# Xbee_shield_v15.net
KiCad netlist of a schematic drawn in EAGLE
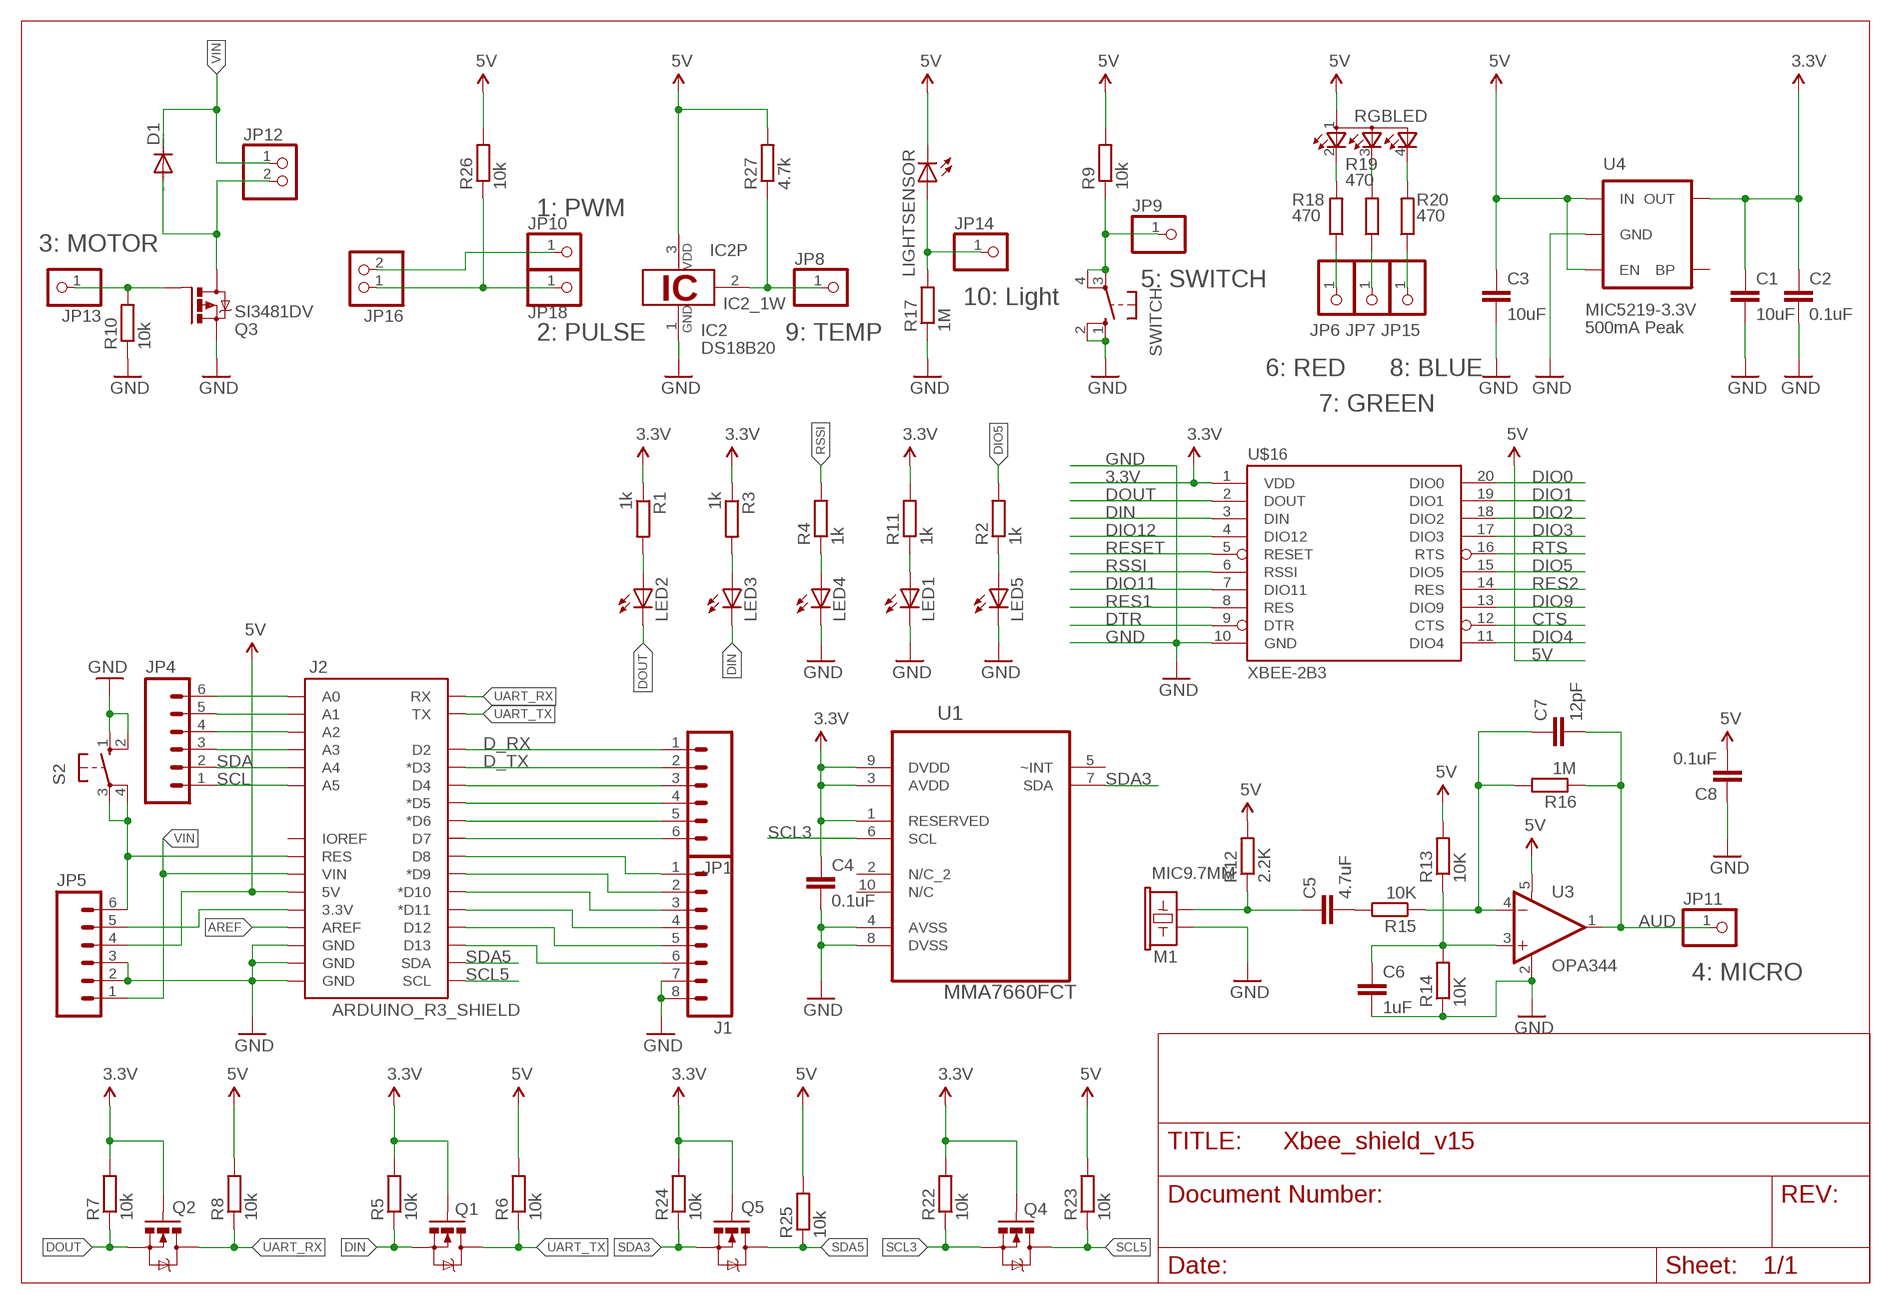
[diagram p0: schematic, sheet 1]

(export (version "E")
  (design (tool "Eeschema 10.0.6"))
  (components
    (comp (ref "C1")
      (value "10uF")
      (footprint "eagle-import:C0805")
      (libsource (lib "eagle-import") (part "C-EUC0805"))
    )
    (comp (ref "C2")
      (value "0.1uF")
      (footprint "eagle-import:C0805")
      (libsource (lib "eagle-import") (part "C-EUC0805"))
    )
    (comp (ref "C3")
      (value "10uF")
      (footprint "eagle-import:C0805")
      (libsource (lib "eagle-import") (part "C-EUC0805"))
    )
    (comp (ref "C4")
      (value "0.1uF")
      (footprint "eagle-import:C0805")
      (libsource (lib "eagle-import") (part "C-EUC0805"))
    )
    (comp (ref "C5")
      (value "4.7uF")
      (footprint "eagle-import:C0805")
      (libsource (lib "eagle-import") (part "C-EUC0805"))
    )
    (comp (ref "C6")
      (value "1uF")
      (footprint "eagle-import:C0805")
      (libsource (lib "eagle-import") (part "C-EUC0805"))
    )
    (comp (ref "C7")
      (value "12pF")
      (footprint "eagle-import:C0805")
      (libsource (lib "eagle-import") (part "C-EUC0805"))
    )
    (comp (ref "C8")
      (value "0.1uF")
      (footprint "eagle-import:C0805")
      (libsource (lib "eagle-import") (part "C-EUC0805"))
    )
    (comp (ref "D1")
      (value "DIODE-DO214AA")
      (footprint "eagle-import:DO214AA")
      (libsource (lib "eagle-import") (part "DIODE-DO214AA"))
    )
    (comp (ref "IC2")
      (value "DS18B20")
      (footprint "eagle-import:TO92-")
      (libsource (lib "eagle-import") (part "DS18B20"))
    )
    (comp (ref "J1")
      (value "M08")
      (footprint "eagle-import:1X08_ROUND")
      (libsource (lib "eagle-import") (part "M08"))
    )
    (comp (ref "J2")
      (value "ARDUINO_R3_SHIELD")
      (footprint "eagle-import:UNO_R3_SHIELD")
      (libsource (lib "eagle-import") (part "ARDUINO_R3_SHIELD"))
    )
    (comp (ref "JP1")
      (value "M06SIP")
      (footprint "eagle-import:1X06")
      (libsource (lib "eagle-import") (part "M06SIP"))
    )
    (comp (ref "JP4")
      (value "M06SIP")
      (footprint "eagle-import:1X06")
      (libsource (lib "eagle-import") (part "M06SIP"))
    )
    (comp (ref "JP5")
      (value "M06SIP")
      (footprint "eagle-import:1X06")
      (libsource (lib "eagle-import") (part "M06SIP"))
    )
    (comp (ref "JP6")
      (value "PINHD-1X1")
      (footprint "eagle-import:1X01")
      (libsource (lib "eagle-import") (part "PINHD-1X1"))
    )
    (comp (ref "JP7")
      (value "PINHD-1X1")
      (footprint "eagle-import:1X01")
      (libsource (lib "eagle-import") (part "PINHD-1X1"))
    )
    (comp (ref "JP8")
      (value "PINHD-1X1")
      (footprint "eagle-import:1X01")
      (libsource (lib "eagle-import") (part "PINHD-1X1"))
    )
    (comp (ref "JP9")
      (value "PINHD-1X1")
      (footprint "eagle-import:1X01")
      (libsource (lib "eagle-import") (part "PINHD-1X1"))
    )
    (comp (ref "JP10")
      (value "PINHD-1X1")
      (footprint "eagle-import:1X01")
      (libsource (lib "eagle-import") (part "PINHD-1X1"))
    )
    (comp (ref "JP11")
      (value "PINHD-1X1")
      (footprint "eagle-import:1X01")
      (libsource (lib "eagle-import") (part "PINHD-1X1"))
    )
    (comp (ref "JP12")
      (value "PINHD-1X2")
      (footprint "eagle-import:1X02")
      (libsource (lib "eagle-import") (part "PINHD-1X2"))
    )
    (comp (ref "JP13")
      (value "PINHD-1X1")
      (footprint "eagle-import:1X01")
      (libsource (lib "eagle-import") (part "PINHD-1X1"))
    )
    (comp (ref "JP14")
      (value "PINHD-1X1")
      (footprint "eagle-import:1X01")
      (libsource (lib "eagle-import") (part "PINHD-1X1"))
    )
    (comp (ref "JP15")
      (value "PINHD-1X1")
      (footprint "eagle-import:1X01")
      (libsource (lib "eagle-import") (part "PINHD-1X1"))
    )
    (comp (ref "JP16")
      (value "PINHD-1X2")
      (footprint "eagle-import:1X02")
      (libsource (lib "eagle-import") (part "PINHD-1X2"))
    )
    (comp (ref "JP18")
      (value "PINHD-1X1")
      (footprint "eagle-import:1X01")
      (libsource (lib "eagle-import") (part "PINHD-1X1"))
    )
    (comp (ref "LED1")
      (value "LEDCHIPLED_0805")
      (footprint "eagle-import:CHIPLED_0805")
      (libsource (lib "eagle-import") (part "LEDCHIPLED_0805"))
    )
    (comp (ref "LED2")
      (value "LEDCHIPLED_0805")
      (footprint "eagle-import:CHIPLED_0805")
      (libsource (lib "eagle-import") (part "LEDCHIPLED_0805"))
    )
    (comp (ref "LED3")
      (value "LEDCHIPLED_0805")
      (footprint "eagle-import:CHIPLED_0805")
      (libsource (lib "eagle-import") (part "LEDCHIPLED_0805"))
    )
    (comp (ref "LED4")
      (value "LEDCHIPLED_0805")
      (footprint "eagle-import:CHIPLED_0805")
      (libsource (lib "eagle-import") (part "LEDCHIPLED_0805"))
    )
    (comp (ref "LED5")
      (value "LEDCHIPLED_0805")
      (footprint "eagle-import:CHIPLED_0805")
      (libsource (lib "eagle-import") (part "LEDCHIPLED_0805"))
    )
    (comp (ref "LIGHTSENSOR")
      (value "LED5MM")
      (footprint "eagle-import:LED5MM")
      (libsource (lib "eagle-import") (part "LED5MM"))
    )
    (comp (ref "M1")
      (value "MIC9.7MM")
      (footprint "eagle-import:MIC-9.7MM")
      (libsource (lib "eagle-import") (part "MIC9.7MM"))
    )
    (comp (ref "Q1")
      (value "MOSFET-NCHANNELSMD")
      (footprint "eagle-import:SOT23-3")
      (libsource (lib "eagle-import") (part "MOSFET-NCHANNELSMD"))
    )
    (comp (ref "Q2")
      (value "MOSFET-NCHANNELSMD")
      (footprint "eagle-import:SOT23-3")
      (libsource (lib "eagle-import") (part "MOSFET-NCHANNELSMD"))
    )
    (comp (ref "Q3")
      (value "SI3481DV")
      (footprint "eagle-import:TSOP-6.PAC")
      (libsource (lib "eagle-import") (part "SI3481DV"))
    )
    (comp (ref "Q4")
      (value "MOSFET-NCHANNELSMD")
      (footprint "eagle-import:SOT23-3")
      (libsource (lib "eagle-import") (part "MOSFET-NCHANNELSMD"))
    )
    (comp (ref "Q5")
      (value "MOSFET-NCHANNELSMD")
      (footprint "eagle-import:SOT23-3")
      (libsource (lib "eagle-import") (part "MOSFET-NCHANNELSMD"))
    )
    (comp (ref "R1")
      (value "1k")
      (footprint "eagle-import:R0805")
      (libsource (lib "eagle-import") (part "R-EU_R0805"))
    )
    (comp (ref "R2")
      (value "1k")
      (footprint "eagle-import:R0805")
      (libsource (lib "eagle-import") (part "R-EU_R0805"))
    )
    (comp (ref "R3")
      (value "1k")
      (footprint "eagle-import:R0805")
      (libsource (lib "eagle-import") (part "R-EU_R0805"))
    )
    (comp (ref "R4")
      (value "1k")
      (footprint "eagle-import:R0805")
      (libsource (lib "eagle-import") (part "R-EU_R0805"))
    )
    (comp (ref "R5")
      (value "10k")
      (footprint "eagle-import:R0805")
      (libsource (lib "eagle-import") (part "R-EU_R0805"))
    )
    (comp (ref "R6")
      (value "10k")
      (footprint "eagle-import:R0805")
      (libsource (lib "eagle-import") (part "R-EU_R0805"))
    )
    (comp (ref "R7")
      (value "10k")
      (footprint "eagle-import:R0805")
      (libsource (lib "eagle-import") (part "R-EU_R0805"))
    )
    (comp (ref "R8")
      (value "10k")
      (footprint "eagle-import:R0805")
      (libsource (lib "eagle-import") (part "R-EU_R0805"))
    )
    (comp (ref "R9")
      (value "10k")
      (footprint "eagle-import:R0805")
      (libsource (lib "eagle-import") (part "R-EU_R0805"))
    )
    (comp (ref "R10")
      (value "10k")
      (footprint "eagle-import:R0805")
      (libsource (lib "eagle-import") (part "R-EU_R0805"))
    )
    (comp (ref "R11")
      (value "1k")
      (footprint "eagle-import:R0805")
      (libsource (lib "eagle-import") (part "R-EU_R0805"))
    )
    (comp (ref "R12")
      (value "2.2K")
      (footprint "eagle-import:R0805")
      (libsource (lib "eagle-import") (part "R-EU_R0805"))
    )
    (comp (ref "R13")
      (value "10K")
      (footprint "eagle-import:R0805")
      (libsource (lib "eagle-import") (part "R-EU_R0805"))
    )
    (comp (ref "R14")
      (value "10K")
      (footprint "eagle-import:R0805")
      (libsource (lib "eagle-import") (part "R-EU_R0805"))
    )
    (comp (ref "R15")
      (value "10K")
      (footprint "eagle-import:R0805")
      (libsource (lib "eagle-import") (part "R-EU_R0805"))
    )
    (comp (ref "R16")
      (value "1M")
      (footprint "eagle-import:R0805")
      (libsource (lib "eagle-import") (part "R-EU_R0805"))
    )
    (comp (ref "R17")
      (value "1M")
      (footprint "eagle-import:R0805")
      (libsource (lib "eagle-import") (part "R-EU_R0805"))
    )
    (comp (ref "R18")
      (value "470")
      (footprint "eagle-import:R0805")
      (libsource (lib "eagle-import") (part "R-EU_R0805"))
    )
    (comp (ref "R19")
      (value "470")
      (footprint "eagle-import:R0805")
      (libsource (lib "eagle-import") (part "R-EU_R0805"))
    )
    (comp (ref "R20")
      (value "470")
      (footprint "eagle-import:R0805")
      (libsource (lib "eagle-import") (part "R-EU_R0805"))
    )
    (comp (ref "R22")
      (value "10k")
      (footprint "eagle-import:R0805")
      (libsource (lib "eagle-import") (part "R-EU_R0805"))
    )
    (comp (ref "R23")
      (value "10k")
      (footprint "eagle-import:R0805")
      (libsource (lib "eagle-import") (part "R-EU_R0805"))
    )
    (comp (ref "R24")
      (value "10k")
      (footprint "eagle-import:R0805")
      (libsource (lib "eagle-import") (part "R-EU_R0805"))
    )
    (comp (ref "R25")
      (value "10k")
      (footprint "eagle-import:R0805")
      (libsource (lib "eagle-import") (part "R-EU_R0805"))
    )
    (comp (ref "R26")
      (value "10k")
      (footprint "eagle-import:R0805")
      (libsource (lib "eagle-import") (part "R-EU_R0805"))
    )
    (comp (ref "R27")
      (value "4.7k")
      (footprint "eagle-import:R0805")
      (libsource (lib "eagle-import") (part "R-EU_R0805"))
    )
    (comp (ref "RGBLED")
      (value "TOPLED-3")
      (footprint "eagle-import:P-LCC-4-3")
      (libsource (lib "eagle-import") (part "TOPLED-3"))
    )
    (comp (ref "S2")
      (value "10-XX")
      (footprint "eagle-import:B3F-10XX")
      (fields (field (name "MPN") "B3F-1000"))
      (libsource (lib "eagle-import") (part "10-XX"))
    )
    (comp (ref "SWITCH")
      (value "10-XX")
      (footprint "eagle-import:B3F-10XX")
      (fields (field (name "MPN") "B3F-1000"))
      (libsource (lib "eagle-import") (part "10-XX"))
    )
    (comp (ref "U$16")
      (value "XBEE-2B3")
      (footprint "eagle-import:XBEE-SMD")
      (libsource (lib "eagle-import") (part "XBEE-2B3"))
    )
    (comp (ref "U1")
      (value "MMA7660FCT")
      (footprint "eagle-import:DFN300X300X100-10N")
      (libsource (lib "eagle-import") (part "MMA7660FCT"))
    )
    (comp (ref "U3")
      (value "OPA344")
      (footprint "eagle-import:SOT23-5")
      (libsource (lib "eagle-import") (part "OPA344"))
    )
    (comp (ref "U4")
      (value "V_REG_LDOSMD")
      (footprint "eagle-import:SOT23-5")
      (libsource (lib "eagle-import") (part "V_REG_LDOSMD"))
    )
  )
  (nets
    (net (code "1") (name "/AUD") (class "Default")
      (node (ref "C7") (pin "2") (pinfunction "2_2") (pintype "passive"))
      (node (ref "JP11") (pin "1") (pinfunction "1_1") (pintype "passive"))
      (node (ref "R16") (pin "1") (pinfunction "1_1") (pintype "passive"))
      (node (ref "U3") (pin "1") (pinfunction "OUT_1") (pintype "output"))
    )
    (net (code "2") (name "/CTS") (class "Default")
      (node (ref "U$16") (pin "12") (pinfunction "CTS_12") (pintype "output"))
    )
    (net (code "3") (name "/DIO0") (class "Default")
      (node (ref "U$16") (pin "20") (pinfunction "DIO0_20") (pintype "bidirectional"))
    )
    (net (code "4") (name "/DIO1") (class "Default")
      (node (ref "U$16") (pin "19") (pinfunction "DIO1_19") (pintype "bidirectional"))
    )
    (net (code "5") (name "/DIO2") (class "Default")
      (node (ref "U$16") (pin "18") (pinfunction "DIO2_18") (pintype "bidirectional"))
    )
    (net (code "6") (name "/DIO3") (class "Default")
      (node (ref "U$16") (pin "17") (pinfunction "DIO3_17") (pintype "bidirectional"))
    )
    (net (code "7") (name "/DIO4") (class "Default")
      (node (ref "U$16") (pin "11") (pinfunction "DIO4_11") (pintype "bidirectional"))
    )
    (net (code "8") (name "/DIO9") (class "Default")
      (node (ref "U$16") (pin "13") (pinfunction "DIO9_13") (pintype "bidirectional"))
    )
    (net (code "9") (name "/DIO11") (class "Default")
      (node (ref "U$16") (pin "7") (pinfunction "DIO11_7") (pintype "bidirectional"))
    )
    (net (code "10") (name "/DIO12") (class "Default")
      (node (ref "U$16") (pin "4") (pinfunction "DIO12_4") (pintype "bidirectional"))
    )
    (net (code "11") (name "/DTR") (class "Default")
      (node (ref "U$16") (pin "9") (pinfunction "DTR_9") (pintype "bidirectional"))
    )
    (net (code "12") (name "/D_RX") (class "Default")
      (node (ref "J2") (pin "D2") (pinfunction "D2_D2") (pintype "bidirectional"))
      (node (ref "JP1") (pin "1") (pinfunction "1_1") (pintype "passive"))
    )
    (net (code "13") (name "/D_TX") (class "Default")
      (node (ref "J2") (pin "D3") (pinfunction "*D3_D3") (pintype "bidirectional"))
      (node (ref "JP1") (pin "2") (pinfunction "2_2") (pintype "passive"))
    )
    (net (code "14") (name "/RES1") (class "Default")
      (node (ref "U$16") (pin "8") (pinfunction "RES_8") (pintype "bidirectional"))
    )
    (net (code "15") (name "/RES2") (class "Default")
      (node (ref "U$16") (pin "14") (pinfunction "RES_14") (pintype "bidirectional"))
    )
    (net (code "16") (name "/RESET") (class "Default")
      (node (ref "U$16") (pin "5") (pinfunction "RESET_5") (pintype "input"))
    )
    (net (code "17") (name "/RTS") (class "Default")
      (node (ref "U$16") (pin "16") (pinfunction "RTS_16") (pintype "input"))
    )
    (net (code "18") (name "/SCL") (class "Default")
      (node (ref "J2") (pin "A5") (pinfunction "A5_A5") (pintype "bidirectional"))
      (node (ref "JP4") (pin "1") (pinfunction "1_1") (pintype "passive"))
    )
    (net (code "19") (name "/SDA") (class "Default")
      (node (ref "J2") (pin "A4") (pinfunction "A4_A4") (pintype "bidirectional"))
      (node (ref "JP4") (pin "2") (pinfunction "2_2") (pintype "passive"))
    )
    (net (code "20") (name "3.3V") (class "Default")
      (node (ref "C1") (pin "1") (pinfunction "1_1") (pintype "passive"))
      (node (ref "C2") (pin "1") (pinfunction "1_1") (pintype "passive"))
      (node (ref "C4") (pin "1") (pinfunction "1_1") (pintype "passive"))
      (node (ref "Q1") (pin "1") (pinfunction "G_1") (pintype "passive"))
      (node (ref "Q2") (pin "1") (pinfunction "G_1") (pintype "passive"))
      (node (ref "Q4") (pin "1") (pinfunction "G_1") (pintype "passive"))
      (node (ref "Q5") (pin "1") (pinfunction "G_1") (pintype "passive"))
      (node (ref "R1") (pin "1") (pinfunction "1_1") (pintype "passive"))
      (node (ref "R11") (pin "2") (pinfunction "2_2") (pintype "passive"))
      (node (ref "R22") (pin "2") (pinfunction "2_2") (pintype "passive"))
      (node (ref "R24") (pin "2") (pinfunction "2_2") (pintype "passive"))
      (node (ref "R3") (pin "1") (pinfunction "1_1") (pintype "passive"))
      (node (ref "R5") (pin "2") (pinfunction "2_2") (pintype "passive"))
      (node (ref "R7") (pin "2") (pinfunction "2_2") (pintype "passive"))
      (node (ref "U$16") (pin "1") (pinfunction "VDD_1") (pintype "power_in"))
      (node (ref "U1") (pin "1") (pinfunction "RESERVED_1") (pintype "passive"))
      (node (ref "U1") (pin "3") (pinfunction "AVDD_3") (pintype "power_in"))
      (node (ref "U1") (pin "9") (pinfunction "DVDD_9") (pintype "power_in"))
      (node (ref "U4") (pin "5") (pinfunction "OUT_5") (pintype "passive"))
    )
    (net (code "21") (name "5V") (class "Default")
      (node (ref "C3") (pin "1") (pinfunction "1_1") (pintype "passive"))
      (node (ref "C8") (pin "2") (pinfunction "2_2") (pintype "passive"))
      (node (ref "IC2") (pin "3") (pinfunction "VDD_3") (pintype "power_in"))
      (node (ref "J2") (pin "5V") (pinfunction "5V_5V") (pintype "bidirectional"))
      (node (ref "JP5") (pin "4") (pinfunction "4_4") (pintype "passive"))
      (node (ref "LIGHTSENSOR") (pin "K") (pinfunction "C_K") (pintype "passive"))
      (node (ref "R12") (pin "2") (pinfunction "2_2") (pintype "passive"))
      (node (ref "R13") (pin "2") (pinfunction "2_2") (pintype "passive"))
      (node (ref "R23") (pin "2") (pinfunction "2_2") (pintype "passive"))
      (node (ref "R25") (pin "2") (pinfunction "2_2") (pintype "passive"))
      (node (ref "R26") (pin "2") (pinfunction "2_2") (pintype "passive"))
      (node (ref "R27") (pin "2") (pinfunction "2_2") (pintype "passive"))
      (node (ref "R6") (pin "2") (pinfunction "2_2") (pintype "passive"))
      (node (ref "R8") (pin "2") (pinfunction "2_2") (pintype "passive"))
      (node (ref "R9") (pin "2") (pinfunction "2_2") (pintype "passive"))
      (node (ref "RGBLED") (pin "1") (pinfunction "A2_1") (pintype "passive"))
      (node (ref "U3") (pin "5") (pinfunction "V+_5") (pintype "power_in"))
      (node (ref "U4") (pin "1") (pinfunction "IN_1") (pintype "input"))
      (node (ref "U4") (pin "3") (pinfunction "EN_3") (pintype "input"))
    )
    (net (code "22") (name "AREF") (class "Default")
      (node (ref "J2") (pin "AREF") (pinfunction "AREF_AREF") (pintype "bidirectional"))
    )
    (net (code "23") (name "DIN") (class "Default")
      (node (ref "LED3") (pin "C") (pinfunction "C_C") (pintype "passive"))
      (node (ref "Q1") (pin "2") (pinfunction "S_2") (pintype "passive"))
      (node (ref "R5") (pin "1") (pinfunction "1_1") (pintype "passive"))
      (node (ref "U$16") (pin "3") (pinfunction "DIN_3") (pintype "input"))
    )
    (net (code "24") (name "DIO5") (class "Default")
      (node (ref "R2") (pin "2") (pinfunction "2_2") (pintype "passive"))
      (node (ref "U$16") (pin "15") (pinfunction "DIO5_15") (pintype "bidirectional"))
    )
    (net (code "25") (name "DOUT") (class "Default")
      (node (ref "LED2") (pin "C") (pinfunction "C_C") (pintype "passive"))
      (node (ref "Q2") (pin "2") (pinfunction "S_2") (pintype "passive"))
      (node (ref "R7") (pin "1") (pinfunction "1_1") (pintype "passive"))
      (node (ref "U$16") (pin "2") (pinfunction "DOUT_2") (pintype "output"))
    )
    (net (code "26") (name "GND") (class "Default")
      (node (ref "C1") (pin "2") (pinfunction "2_2") (pintype "passive"))
      (node (ref "C2") (pin "2") (pinfunction "2_2") (pintype "passive"))
      (node (ref "C3") (pin "2") (pinfunction "2_2") (pintype "passive"))
      (node (ref "C4") (pin "2") (pinfunction "2_2") (pintype "passive"))
      (node (ref "C6") (pin "2") (pinfunction "2_2") (pintype "passive"))
      (node (ref "C8") (pin "1") (pinfunction "1_1") (pintype "passive"))
      (node (ref "IC2") (pin "1") (pinfunction "GND_1") (pintype "power_in"))
      (node (ref "J1") (pin "7") (pinfunction "7_7") (pintype "passive"))
      (node (ref "J1") (pin "8") (pinfunction "8_8") (pintype "passive"))
      (node (ref "J2") (pin "GND@0") (pinfunction "GND_GND@0") (pintype "bidirectional"))
      (node (ref "J2") (pin "GND@1") (pinfunction "GND_GND@1") (pintype "bidirectional"))
      (node (ref "J2") (pin "GND@2") (pinfunction "GND_GND@2") (pintype "bidirectional"))
      (node (ref "JP5") (pin "2") (pinfunction "2_2") (pintype "passive"))
      (node (ref "JP5") (pin "3") (pinfunction "3_3") (pintype "passive"))
      (node (ref "LED1") (pin "C") (pinfunction "C_C") (pintype "passive"))
      (node (ref "LED4") (pin "C") (pinfunction "C_C") (pintype "passive"))
      (node (ref "LED5") (pin "C") (pinfunction "C_C") (pintype "passive"))
      (node (ref "M1") (pin "2") (pinfunction "2_2") (pintype "passive"))
      (node (ref "Q3") (pin "4") (pinfunction "S_4") (pintype "passive"))
      (node (ref "R10") (pin "1") (pinfunction "1_1") (pintype "passive"))
      (node (ref "R14") (pin "1") (pinfunction "1_1") (pintype "passive"))
      (node (ref "R17") (pin "1") (pinfunction "1_1") (pintype "passive"))
      (node (ref "S2") (pin "1") (pinfunction "S_1") (pintype "passive"))
      (node (ref "S2") (pin "2") (pinfunction "S1_2") (pintype "passive"))
      (node (ref "SWITCH") (pin "1") (pinfunction "S_1") (pintype "passive"))
      (node (ref "SWITCH") (pin "2") (pinfunction "S1_2") (pintype "passive"))
      (node (ref "U$16") (pin "10") (pinfunction "GND_10") (pintype "power_in"))
      (node (ref "U1") (pin "4") (pinfunction "AVSS_4") (pintype "power_in"))
      (node (ref "U1") (pin "8") (pinfunction "DVSS_8") (pintype "power_in"))
      (node (ref "U3") (pin "2") (pinfunction "V-_2") (pintype "power_in"))
      (node (ref "U4") (pin "2") (pinfunction "GND_2") (pintype "input"))
    )
    (net (code "27") (name "Net-(C5-Pad1)") (class "Default")
      (node (ref "C5") (pin "1") (pinfunction "1_1") (pintype "passive"))
      (node (ref "M1") (pin "1") (pinfunction "1_1") (pintype "passive"))
      (node (ref "R12") (pin "1") (pinfunction "1_1") (pintype "passive"))
    )
    (net (code "28") (name "Net-(C5-Pad2)") (class "Default")
      (node (ref "C5") (pin "2") (pinfunction "2_2") (pintype "passive"))
      (node (ref "R15") (pin "2") (pinfunction "2_2") (pintype "passive"))
    )
    (net (code "29") (name "Net-(D1-PadA)") (class "Default")
      (node (ref "D1") (pin "A") (pinfunction "A_A") (pintype "passive"))
      (node (ref "JP12") (pin "2") (pinfunction "2_2") (pintype "passive"))
      (node (ref "Q3") (pin "1") (pinfunction "D_1") (pintype "passive"))
      (node (ref "Q3") (pin "2") (pinfunction "D_2") (pintype "passive"))
      (node (ref "Q3") (pin "5") (pinfunction "D_5") (pintype "passive"))
      (node (ref "Q3") (pin "6") (pinfunction "D_6") (pintype "passive"))
    )
    (net (code "30") (name "Net-(IC2C-1W)") (class "Default")
      (node (ref "IC2") (pin "2") (pinfunction "1W_2") (pintype "power_in"))
      (node (ref "JP8") (pin "1") (pinfunction "1_1") (pintype "passive"))
      (node (ref "R27") (pin "1") (pinfunction "1_1") (pintype "passive"))
    )
    (net (code "31") (name "Net-(J1-Pad1)") (class "Default")
      (node (ref "J1") (pin "1") (pinfunction "1_1") (pintype "passive"))
      (node (ref "J2") (pin "D8") (pinfunction "D8_D8") (pintype "bidirectional"))
    )
    (net (code "32") (name "Net-(J1-Pad5)") (class "Default")
      (node (ref "J1") (pin "5") (pinfunction "5_5") (pintype "passive"))
      (node (ref "J2") (pin "D12") (pinfunction "D12_D12") (pintype "bidirectional"))
    )
    (net (code "33") (name "Net-(J1-Pad6)") (class "Default")
      (node (ref "J1") (pin "6") (pinfunction "6_6") (pintype "passive"))
      (node (ref "J2") (pin "D13") (pinfunction "D13_D13") (pintype "bidirectional"))
    )
    (net (code "34") (name "Net-(J2-*D5)") (class "Default")
      (node (ref "J2") (pin "D5") (pinfunction "*D5_D5") (pintype "bidirectional"))
      (node (ref "JP1") (pin "4") (pinfunction "4_4") (pintype "passive"))
    )
    (net (code "35") (name "Net-(J2-*D6)") (class "Default")
      (node (ref "J2") (pin "D6") (pinfunction "*D6_D6") (pintype "bidirectional"))
      (node (ref "JP1") (pin "5") (pinfunction "5_5") (pintype "passive"))
    )
    (net (code "36") (name "Net-(J2-*D9)") (class "Default")
      (node (ref "J1") (pin "2") (pinfunction "2_2") (pintype "passive"))
      (node (ref "J2") (pin "D9") (pinfunction "*D9_D9") (pintype "bidirectional"))
    )
    (net (code "37") (name "Net-(J2-*D10)") (class "Default")
      (node (ref "J1") (pin "3") (pinfunction "3_3") (pintype "passive"))
      (node (ref "J2") (pin "D10") (pinfunction "*D10_D10") (pintype "bidirectional"))
    )
    (net (code "38") (name "Net-(J2-*D11)") (class "Default")
      (node (ref "J1") (pin "4") (pinfunction "4_4") (pintype "passive"))
      (node (ref "J2") (pin "D11") (pinfunction "*D11_D11") (pintype "bidirectional"))
    )
    (net (code "39") (name "Net-(J2-Pad3.3V)") (class "Default")
      (node (ref "J2") (pin "3.3V") (pinfunction "3.3V_3.3V") (pintype "bidirectional"))
      (node (ref "JP5") (pin "5") (pinfunction "5_5") (pintype "passive"))
    )
    (net (code "40") (name "Net-(J2-PadA0)") (class "Default")
      (node (ref "J2") (pin "A0") (pinfunction "A0_A0") (pintype "bidirectional"))
      (node (ref "JP4") (pin "6") (pinfunction "6_6") (pintype "passive"))
    )
    (net (code "41") (name "Net-(J2-PadA1)") (class "Default")
      (node (ref "J2") (pin "A1") (pinfunction "A1_A1") (pintype "bidirectional"))
      (node (ref "JP4") (pin "5") (pinfunction "5_5") (pintype "passive"))
    )
    (net (code "42") (name "Net-(J2-PadA2)") (class "Default")
      (node (ref "J2") (pin "A2") (pinfunction "A2_A2") (pintype "bidirectional"))
      (node (ref "JP4") (pin "4") (pinfunction "4_4") (pintype "passive"))
    )
    (net (code "43") (name "Net-(J2-PadA3)") (class "Default")
      (node (ref "J2") (pin "A3") (pinfunction "A3_A3") (pintype "bidirectional"))
      (node (ref "JP4") (pin "3") (pinfunction "3_3") (pintype "passive"))
    )
    (net (code "44") (name "Net-(J2-PadD4)") (class "Default")
      (node (ref "J2") (pin "D4") (pinfunction "D4_D4") (pintype "bidirectional"))
      (node (ref "JP1") (pin "3") (pinfunction "3_3") (pintype "passive"))
    )
    (net (code "45") (name "Net-(J2-PadD7)") (class "Default")
      (node (ref "J2") (pin "D7") (pinfunction "D7_D7") (pintype "bidirectional"))
      (node (ref "JP1") (pin "6") (pinfunction "6_6") (pintype "passive"))
    )
    (net (code "46") (name "Net-(JP6-Pad1)") (class "Default")
      (node (ref "JP6") (pin "1") (pinfunction "1_1") (pintype "passive"))
      (node (ref "R18") (pin "1") (pinfunction "1_1") (pintype "passive"))
    )
    (net (code "47") (name "Net-(JP7-Pad1)") (class "Default")
      (node (ref "JP7") (pin "1") (pinfunction "1_1") (pintype "passive"))
      (node (ref "R19") (pin "1") (pinfunction "1_1") (pintype "passive"))
    )
    (net (code "48") (name "Net-(JP10-Pad1)") (class "Default")
      (node (ref "JP10") (pin "1") (pinfunction "1_1") (pintype "passive"))
      (node (ref "JP16") (pin "2") (pinfunction "2_2") (pintype "passive"))
    )
    (net (code "49") (name "Net-(JP14-Pad1)") (class "Default")
      (node (ref "JP14") (pin "1") (pinfunction "1_1") (pintype "passive"))
      (node (ref "LIGHTSENSOR") (pin "A") (pinfunction "A_A") (pintype "passive"))
      (node (ref "R17") (pin "2") (pinfunction "2_2") (pintype "passive"))
    )
    (net (code "50") (name "Net-(JP15-Pad1)") (class "Default")
      (node (ref "JP15") (pin "1") (pinfunction "1_1") (pintype "passive"))
      (node (ref "R20") (pin "1") (pinfunction "1_1") (pintype "passive"))
    )
    (net (code "51") (name "Net-(JP16-Pad1)") (class "Default")
      (node (ref "JP16") (pin "1") (pinfunction "1_1") (pintype "passive"))
      (node (ref "JP18") (pin "1") (pinfunction "1_1") (pintype "passive"))
      (node (ref "R26") (pin "1") (pinfunction "1_1") (pintype "passive"))
    )
    (net (code "52") (name "Net-(LED1-PadA)") (class "Default")
      (node (ref "LED1") (pin "A") (pinfunction "A_A") (pintype "passive"))
      (node (ref "R11") (pin "1") (pinfunction "1_1") (pintype "passive"))
    )
    (net (code "53") (name "Net-(LED2-PadA)") (class "Default")
      (node (ref "LED2") (pin "A") (pinfunction "A_A") (pintype "passive"))
      (node (ref "R1") (pin "2") (pinfunction "2_2") (pintype "passive"))
    )
    (net (code "54") (name "Net-(LED3-PadA)") (class "Default")
      (node (ref "LED3") (pin "A") (pinfunction "A_A") (pintype "passive"))
      (node (ref "R3") (pin "2") (pinfunction "2_2") (pintype "passive"))
    )
    (net (code "55") (name "Net-(LED4-PadA)") (class "Default")
      (node (ref "LED4") (pin "A") (pinfunction "A_A") (pintype "passive"))
      (node (ref "R4") (pin "1") (pinfunction "1_1") (pintype "passive"))
    )
    (net (code "56") (name "Net-(LED5-PadA)") (class "Default")
      (node (ref "LED5") (pin "A") (pinfunction "A_A") (pintype "passive"))
      (node (ref "R2") (pin "1") (pinfunction "1_1") (pintype "passive"))
    )
    (net (code "57") (name "Net-(Q3-G)") (class "Default")
      (node (ref "JP13") (pin "1") (pinfunction "1_1") (pintype "passive"))
      (node (ref "Q3") (pin "3") (pinfunction "G_3") (pintype "passive"))
      (node (ref "R10") (pin "2") (pinfunction "2_2") (pintype "passive"))
    )
    (net (code "58") (name "Net-(RGBLED-CBLUE)") (class "Default")
      (node (ref "R19") (pin "2") (pinfunction "2_2") (pintype "passive"))
      (node (ref "RGBLED") (pin "3") (pinfunction "CBLUE_3") (pintype "passive"))
    )
    (net (code "59") (name "Net-(RGBLED-CGREEN)") (class "Default")
      (node (ref "R20") (pin "2") (pinfunction "2_2") (pintype "passive"))
      (node (ref "RGBLED") (pin "4") (pinfunction "CGREEN_4") (pintype "passive"))
    )
    (net (code "60") (name "Net-(RGBLED-CRED)") (class "Default")
      (node (ref "R18") (pin "2") (pinfunction "2_2") (pintype "passive"))
      (node (ref "RGBLED") (pin "2") (pinfunction "CRED_2") (pintype "passive"))
    )
    (net (code "61") (name "Net-(S2-P)") (class "Default")
      (node (ref "J2") (pin "RES") (pinfunction "RES_RES") (pintype "bidirectional"))
      (node (ref "JP5") (pin "6") (pinfunction "6_6") (pintype "passive"))
      (node (ref "S2") (pin "3") (pinfunction "P_3") (pintype "passive"))
      (node (ref "S2") (pin "4") (pinfunction "P1_4") (pintype "passive"))
    )
    (net (code "62") (name "Net-(SWITCH-P)") (class "Default")
      (node (ref "JP9") (pin "1") (pinfunction "1_1") (pintype "passive"))
      (node (ref "R9") (pin "1") (pinfunction "1_1") (pintype "passive"))
      (node (ref "SWITCH") (pin "3") (pinfunction "P_3") (pintype "passive"))
      (node (ref "SWITCH") (pin "4") (pinfunction "P1_4") (pintype "passive"))
    )
    (net (code "63") (name "Net-(U3-+IN)") (class "Default")
      (node (ref "C6") (pin "1") (pinfunction "1_1") (pintype "passive"))
      (node (ref "R13") (pin "1") (pinfunction "1_1") (pintype "passive"))
      (node (ref "R14") (pin "2") (pinfunction "2_2") (pintype "passive"))
      (node (ref "U3") (pin "3") (pinfunction "+IN_3") (pintype "input"))
    )
    (net (code "64") (name "Net-(U3--IN)") (class "Default")
      (node (ref "C7") (pin "1") (pinfunction "1_1") (pintype "passive"))
      (node (ref "R15") (pin "1") (pinfunction "1_1") (pintype "passive"))
      (node (ref "R16") (pin "2") (pinfunction "2_2") (pintype "passive"))
      (node (ref "U3") (pin "4") (pinfunction "-IN_4") (pintype "input"))
    )
    (net (code "65") (name "RSSI") (class "Default")
      (node (ref "R4") (pin "2") (pinfunction "2_2") (pintype "passive"))
      (node (ref "U$16") (pin "6") (pinfunction "RSSI_6") (pintype "bidirectional"))
    )
    (net (code "66") (name "SCL3") (class "Default")
      (node (ref "Q4") (pin "2") (pinfunction "S_2") (pintype "passive"))
      (node (ref "R22") (pin "1") (pinfunction "1_1") (pintype "passive"))
      (node (ref "U1") (pin "6") (pinfunction "SCL_6") (pintype "input"))
    )
    (net (code "67") (name "SCL5") (class "Default")
      (node (ref "J2") (pin "SCL") (pinfunction "SCL_SCL") (pintype "bidirectional"))
      (node (ref "Q4") (pin "3") (pinfunction "D_3") (pintype "passive"))
      (node (ref "R23") (pin "1") (pinfunction "1_1") (pintype "passive"))
    )
    (net (code "68") (name "SDA3") (class "Default")
      (node (ref "Q5") (pin "2") (pinfunction "S_2") (pintype "passive"))
      (node (ref "R24") (pin "1") (pinfunction "1_1") (pintype "passive"))
      (node (ref "U1") (pin "7") (pinfunction "SDA_7") (pintype "bidirectional"))
    )
    (net (code "69") (name "SDA5") (class "Default")
      (node (ref "J2") (pin "SDA") (pinfunction "SDA_SDA") (pintype "bidirectional"))
      (node (ref "Q5") (pin "3") (pinfunction "D_3") (pintype "passive"))
      (node (ref "R25") (pin "1") (pinfunction "1_1") (pintype "passive"))
    )
    (net (code "70") (name "UART_RX") (class "Default")
      (node (ref "J2") (pin "RX") (pinfunction "RX_RX") (pintype "bidirectional"))
      (node (ref "Q2") (pin "3") (pinfunction "D_3") (pintype "passive"))
      (node (ref "R8") (pin "1") (pinfunction "1_1") (pintype "passive"))
    )
    (net (code "71") (name "UART_TX") (class "Default")
      (node (ref "J2") (pin "TX") (pinfunction "TX_TX") (pintype "bidirectional"))
      (node (ref "Q1") (pin "3") (pinfunction "D_3") (pintype "passive"))
      (node (ref "R6") (pin "1") (pinfunction "1_1") (pintype "passive"))
    )
    (net (code "72") (name "VIN") (class "Default")
      (node (ref "D1") (pin "C") (pinfunction "C_C") (pintype "passive"))
      (node (ref "J2") (pin "VIN") (pinfunction "VIN_VIN") (pintype "bidirectional"))
      (node (ref "JP12") (pin "1") (pinfunction "1_1") (pintype "passive"))
      (node (ref "JP5") (pin "1") (pinfunction "1_1") (pintype "passive"))
    )
    (net (code "73") (name "unconnected-(J2-PadIOREF)") (class "Default")
      (node (ref "J2") (pin "IOREF") (pinfunction "IOREF_IOREF") (pintype "bidirectional"))
    )
    (net (code "74") (name "unconnected-(U1-N{slash}C-Pad10)") (class "Default")
      (node (ref "U1") (pin "10") (pinfunction "N/C_10") (pintype "no_connect"))
    )
    (net (code "75") (name "unconnected-(U1-N{slash}C_2-Pad2)") (class "Default")
      (node (ref "U1") (pin "2") (pinfunction "N/C_2_2") (pintype "no_connect"))
    )
    (net (code "76") (name "unconnected-(U1-~{INT}-Pad5)") (class "Default")
      (node (ref "U1") (pin "5") (pinfunction "~{INT}_5") (pintype "output"))
    )
    (net (code "77") (name "unconnected-(U4-BP-Pad4)") (class "Default")
      (node (ref "U4") (pin "4") (pinfunction "BP_4") (pintype "input"))
    )
  )
)
